# DIY_Arduino_-_REV_1.net
KiCad netlist of a schematic drawn in EAGLE
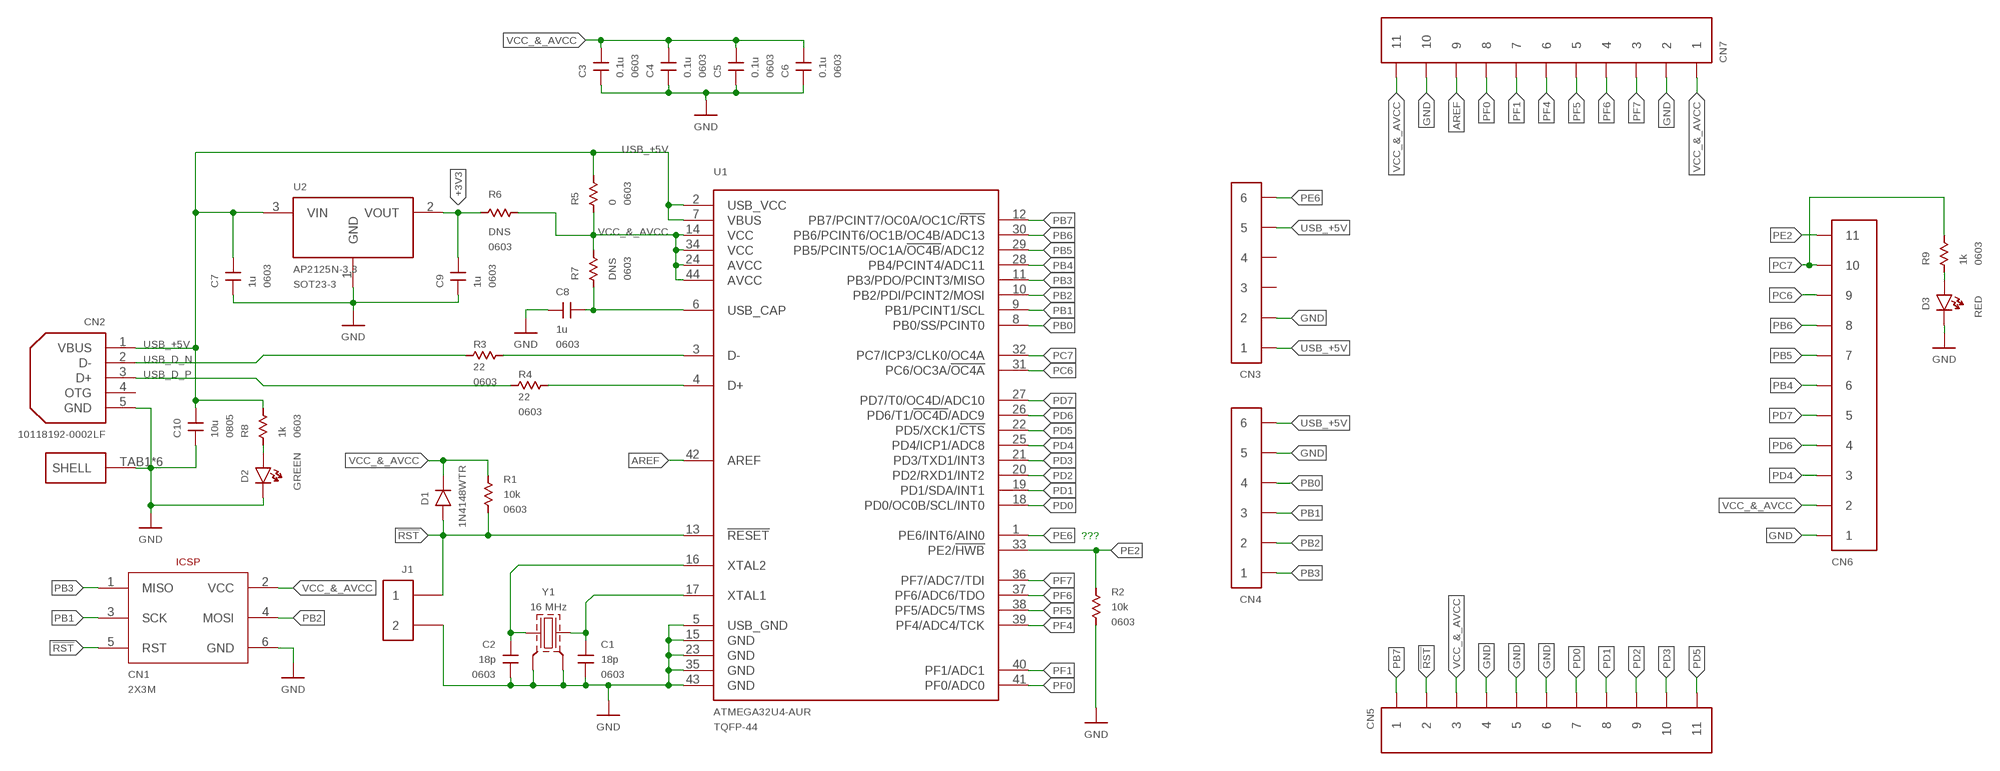
[diagram p0: schematic, sheet 1]

(export (version "E")
  (design (tool "Eeschema 10.0.6"))
  (components
    (comp (ref "C1")
      (value "18p")
      (footprint "eagle-import:EIA0603")
      (fields (field (name "PACKAGE") "0603") (field (name "MPN") "C0603C180J5GACTU"))
      (libsource (lib "eagle-import") (part "C_SMDC0603"))
    )
    (comp (ref "C2")
      (value "18p")
      (footprint "eagle-import:EIA0603")
      (fields (field (name "PACKAGE") "0603") (field (name "MPN") "C0603C180J5GACTU"))
      (libsource (lib "eagle-import") (part "C_SMDC0603"))
    )
    (comp (ref "C3")
      (value "0.1u")
      (footprint "eagle-import:EIA0603")
      (fields (field (name "PACKAGE") "0603") (field (name "MPN") "CL10B104KB8NNNC"))
      (libsource (lib "eagle-import") (part "C_SMDC0603"))
    )
    (comp (ref "C4")
      (value "0.1u")
      (footprint "eagle-import:EIA0603")
      (fields (field (name "PACKAGE") "0603") (field (name "MPN") "CL10B104KB8NNNC"))
      (libsource (lib "eagle-import") (part "C_SMDC0603"))
    )
    (comp (ref "C5")
      (value "0.1u")
      (footprint "eagle-import:EIA0603")
      (fields (field (name "PACKAGE") "0603") (field (name "MPN") "CL10B104KB8NNNC"))
      (libsource (lib "eagle-import") (part "C_SMDC0603"))
    )
    (comp (ref "C6")
      (value "0.1u")
      (footprint "eagle-import:EIA0603")
      (fields (field (name "PACKAGE") "0603") (field (name "MPN") "CL10B104KB8NNNC"))
      (libsource (lib "eagle-import") (part "C_SMDC0603"))
    )
    (comp (ref "C7")
      (value "1u")
      (footprint "eagle-import:EIA0603")
      (fields (field (name "PACKAGE") "0603") (field (name "MPN") "CL10B105KP8NNNC"))
      (libsource (lib "eagle-import") (part "C_SMDC0603"))
    )
    (comp (ref "C8")
      (value "1u")
      (footprint "eagle-import:EIA0603")
      (fields (field (name "PACKAGE") "0603") (field (name "MPN") "CL10B105KP8NNNC"))
      (libsource (lib "eagle-import") (part "C_SMDC0603"))
    )
    (comp (ref "C9")
      (value "1u")
      (footprint "eagle-import:EIA0603")
      (fields (field (name "PACKAGE") "0603") (field (name "MPN") "CL10B105KP8NNNC"))
      (libsource (lib "eagle-import") (part "C_SMDC0603"))
    )
    (comp (ref "C10")
      (value "10u")
      (footprint "eagle-import:EIA0805")
      (fields (field (name "PACKAGE") "0805") (field (name "MPN") "CL21A106KOFNNNE"))
      (libsource (lib "eagle-import") (part "C_SMDC0805"))
    )
    (comp (ref "CN1")
      (value "2X3M")
      (footprint "eagle-import:2X3_100MIL_ICSP")
      (fields (field (name "MPN") "PH2-06-UA"))
      (libsource (lib "eagle-import") (part "2X3_ICSPARDUINO_ICSP"))
    )
    (comp (ref "CN2")
      (value "10118192-0002LF")
      (footprint "eagle-import:AMPHENOL_10118192-0002LF")
      (fields (field (name "MPN") "10118192-0002LF"))
      (libsource (lib "eagle-import") (part "USB_MICRO_B_GENERICSMT"))
    )
    (comp (ref "CN3")
      (value "1X6THRU")
      (footprint "eagle-import:1X6_100MIL_THRU")
      (libsource (lib "eagle-import") (part "1X6THRU"))
    )
    (comp (ref "CN4")
      (value "1X6THRU")
      (footprint "eagle-import:1X6_100MIL_THRU")
      (libsource (lib "eagle-import") (part "1X6THRU"))
    )
    (comp (ref "CN5")
      (value "1X11")
      (footprint "eagle-import:1X11_100MIL_THRU")
      (libsource (lib "eagle-import") (part "1X11"))
    )
    (comp (ref "CN6")
      (value "1X11")
      (footprint "eagle-import:1X11_100MIL_THRU")
      (libsource (lib "eagle-import") (part "1X11"))
    )
    (comp (ref "CN7")
      (value "1X11")
      (footprint "eagle-import:1X11_100MIL_THRU")
      (libsource (lib "eagle-import") (part "1X11"))
    )
    (comp (ref "D1")
      (value "1N4148WTR")
      (footprint "eagle-import:SOD-123")
      (fields (field (name "MPN") "1N4148WTR"))
      (libsource (lib "eagle-import") (part "SILICON"))
    )
    (comp (ref "D2")
      (value "GREEN")
      (footprint "eagle-import:EIA0603_LED")
      (fields (field (name "MPN") "HSME-C191"))
      (libsource (lib "eagle-import") (part "LED_SMD"))
    )
    (comp (ref "D3")
      (value "RED")
      (footprint "eagle-import:EIA0603_LED")
      (fields (field (name "MPN") "ASMT-RR45-AQ902"))
      (libsource (lib "eagle-import") (part "LED_SMD"))
    )
    (comp (ref "J1")
      (value "1X2")
      (footprint "eagle-import:1X2_100MIL_THRU")
      (libsource (lib "eagle-import") (part "1X2"))
    )
    (comp (ref "R1")
      (value "10k")
      (footprint "eagle-import:EIA0603")
      (fields (field (name "PACKAGE") "0603") (field (name "MPN") "ERJ-3EKF1002V"))
      (libsource (lib "eagle-import") (part "R_SMDR0603"))
    )
    (comp (ref "R2")
      (value "10k")
      (footprint "eagle-import:EIA0603")
      (fields (field (name "PACKAGE") "0603") (field (name "MPN") "ERJ-3EKF1002V"))
      (libsource (lib "eagle-import") (part "R_SMDR0603"))
    )
    (comp (ref "R3")
      (value "22")
      (footprint "eagle-import:EIA0603")
      (fields (field (name "PACKAGE") "0603") (field (name "MPN") "ERJ-3EKF22R0V"))
      (libsource (lib "eagle-import") (part "R_SMDR0603"))
    )
    (comp (ref "R4")
      (value "22")
      (footprint "eagle-import:EIA0603")
      (fields (field (name "PACKAGE") "0603") (field (name "MPN") "ERJ-3EKF22R0V"))
      (libsource (lib "eagle-import") (part "R_SMDR0603"))
    )
    (comp (ref "R5")
      (value "0")
      (footprint "eagle-import:EIA0603")
      (fields (field (name "PACKAGE") "0603") (field (name "MPN") "RMCF0603ZT0R00"))
      (libsource (lib "eagle-import") (part "R_SMDR0603"))
    )
    (comp (ref "R6")
      (value "DNS")
      (footprint "eagle-import:EIA0603")
      (fields (field (name "PACKAGE") "0603"))
      (libsource (lib "eagle-import") (part "R_SMDR0603"))
    )
    (comp (ref "R7")
      (value "DNS")
      (footprint "eagle-import:EIA0603")
      (fields (field (name "PACKAGE") "0603"))
      (libsource (lib "eagle-import") (part "R_SMDR0603"))
    )
    (comp (ref "R8")
      (value "1k")
      (footprint "eagle-import:EIA0603")
      (fields (field (name "PACKAGE") "0603") (field (name "MPN") "ERJ-3EKF1001V"))
      (libsource (lib "eagle-import") (part "R_SMDR0603"))
    )
    (comp (ref "R9")
      (value "1k")
      (footprint "eagle-import:EIA0603")
      (fields (field (name "PACKAGE") "0603") (field (name "MPN") "ERJ-3EKF1001V"))
      (libsource (lib "eagle-import") (part "R_SMDR0603"))
    )
    (comp (ref "U1")
      (value "ATMEGA32U4-AUR")
      (footprint "eagle-import:TQFP-44")
      (fields (field (name "PACKAGE") "TQFP-44"))
      (libsource (lib "eagle-import") (part "ATMEGA32U4TQFP-44"))
    )
    (comp (ref "U2")
      (value "AP2125N-3.3")
      (footprint "eagle-import:SOT23-3")
      (fields (field (name "PACKAGE") "SOT23-3") (field (name "MPN") "AP2125N-3.3TRG1"))
      (libsource (lib "eagle-import") (part "AP2125FIXED"))
    )
    (comp (ref "Y1")
      (value "16 MHz")
      (footprint "eagle-import:EPSON_FA-238")
      (fields (field (name "MPN") "FA-238 16.0000MB-C3"))
      (libsource (lib "eagle-import") (part "CRYSTALFA-238"))
    )
  )
  (nets
    (net (code "1") (name "+3V3") (class "Default")
      (node (ref "C9") (pin "P$2") (pinfunction "P$2_P$2") (pintype "passive"))
      (node (ref "R6") (pin "P$1") (pinfunction "P$1_P$1") (pintype "passive"))
      (node (ref "U2") (pin "2") (pinfunction "VOUT_2") (pintype "bidirectional"))
    )
    (net (code "2") (name "/USB_D_N") (class "Default")
      (node (ref "CN2") (pin "2") (pinfunction "D-_2") (pintype "bidirectional"))
      (node (ref "R3") (pin "P$1") (pinfunction "P$1_P$1") (pintype "passive"))
    )
    (net (code "3") (name "/USB_D_P") (class "Default")
      (node (ref "CN2") (pin "3") (pinfunction "D+_3") (pintype "bidirectional"))
      (node (ref "R4") (pin "P$1") (pinfunction "P$1_P$1") (pintype "passive"))
    )
    (net (code "4") (name "/~{RST}") (class "Default")
      (node (ref "CN1") (pin "5") (pinfunction "RST_5") (pintype "bidirectional"))
      (node (ref "CN5") (pin "2") (pinfunction "2_2") (pintype "bidirectional"))
      (node (ref "D1") (pin "A") (pinfunction "A_A") (pintype "bidirectional"))
      (node (ref "J1") (pin "1") (pinfunction "1_1") (pintype "bidirectional"))
      (node (ref "R1") (pin "P$1") (pinfunction "P$1_P$1") (pintype "passive"))
      (node (ref "U1") (pin "13") (pinfunction "~{RESET}_13") (pintype "bidirectional"))
    )
    (net (code "5") (name "AREF") (class "Default")
      (node (ref "CN7") (pin "9") (pinfunction "9_9") (pintype "bidirectional"))
      (node (ref "U1") (pin "42") (pinfunction "AREF_42") (pintype "bidirectional"))
    )
    (net (code "6") (name "GND") (class "Default")
      (node (ref "C1") (pin "P$1") (pinfunction "P$1_P$1") (pintype "passive"))
      (node (ref "C10") (pin "P$1") (pinfunction "P$1_P$1") (pintype "passive"))
      (node (ref "C2") (pin "P$1") (pinfunction "P$1_P$1") (pintype "passive"))
      (node (ref "C3") (pin "P$1") (pinfunction "P$1_P$1") (pintype "passive"))
      (node (ref "C4") (pin "P$1") (pinfunction "P$1_P$1") (pintype "passive"))
      (node (ref "C5") (pin "P$1") (pinfunction "P$1_P$1") (pintype "passive"))
      (node (ref "C6") (pin "P$1") (pinfunction "P$1_P$1") (pintype "passive"))
      (node (ref "C7") (pin "P$1") (pinfunction "P$1_P$1") (pintype "passive"))
      (node (ref "C8") (pin "P$1") (pinfunction "P$1_P$1") (pintype "passive"))
      (node (ref "C9") (pin "P$1") (pinfunction "P$1_P$1") (pintype "passive"))
      (node (ref "CN1") (pin "6") (pinfunction "GND_6") (pintype "bidirectional"))
      (node (ref "CN2") (pin "5") (pinfunction "GND_5") (pintype "bidirectional"))
      (node (ref "CN2") (pin "TAB1") (pinfunction "SHELL_TAB1") (pintype "bidirectional"))
      (node (ref "CN2") (pin "TAB2") (pinfunction "SHELL_TAB2") (pintype "bidirectional"))
      (node (ref "CN2") (pin "TAB3") (pinfunction "SHELL_TAB3") (pintype "bidirectional"))
      (node (ref "CN2") (pin "TAB4") (pinfunction "SHELL_TAB4") (pintype "bidirectional"))
      (node (ref "CN2") (pin "TAB5") (pinfunction "SHELL_TAB5") (pintype "bidirectional"))
      (node (ref "CN2") (pin "TAB6") (pinfunction "SHELL_TAB6") (pintype "bidirectional"))
      (node (ref "CN3") (pin "2") (pinfunction "2_2") (pintype "bidirectional"))
      (node (ref "CN4") (pin "5") (pinfunction "5_5") (pintype "bidirectional"))
      (node (ref "CN5") (pin "4") (pinfunction "4_4") (pintype "bidirectional"))
      (node (ref "CN5") (pin "5") (pinfunction "5_5") (pintype "bidirectional"))
      (node (ref "CN5") (pin "6") (pinfunction "6_6") (pintype "bidirectional"))
      (node (ref "CN6") (pin "1") (pinfunction "1_1") (pintype "bidirectional"))
      (node (ref "CN7") (pin "10") (pinfunction "10_10") (pintype "bidirectional"))
      (node (ref "CN7") (pin "2") (pinfunction "2_2") (pintype "bidirectional"))
      (node (ref "D2") (pin "C") (pinfunction "C_C") (pintype "passive"))
      (node (ref "D3") (pin "C") (pinfunction "C_C") (pintype "passive"))
      (node (ref "J1") (pin "2") (pinfunction "2_2") (pintype "bidirectional"))
      (node (ref "R2") (pin "P$1") (pinfunction "P$1_P$1") (pintype "passive"))
      (node (ref "U1") (pin "15") (pinfunction "GND_15") (pintype "bidirectional"))
      (node (ref "U1") (pin "23") (pinfunction "GND_23") (pintype "bidirectional"))
      (node (ref "U1") (pin "35") (pinfunction "GND_35") (pintype "bidirectional"))
      (node (ref "U1") (pin "43") (pinfunction "GND_43") (pintype "bidirectional"))
      (node (ref "U1") (pin "5") (pinfunction "USB_GND_5") (pintype "bidirectional"))
      (node (ref "U2") (pin "1") (pinfunction "GND_1") (pintype "bidirectional"))
      (node (ref "Y1") (pin "2") (pinfunction "GND_2") (pintype "bidirectional"))
      (node (ref "Y1") (pin "4") (pinfunction "GND_4") (pintype "bidirectional"))
    )
    (net (code "7") (name "Net-(D2-PadA)") (class "Default")
      (node (ref "D2") (pin "A") (pinfunction "A_A") (pintype "passive"))
      (node (ref "R8") (pin "P$1") (pinfunction "P$1_P$1") (pintype "passive"))
    )
    (net (code "8") (name "Net-(D3-PadA)") (class "Default")
      (node (ref "D3") (pin "A") (pinfunction "A_A") (pintype "passive"))
      (node (ref "R9") (pin "P$1") (pinfunction "P$1_P$1") (pintype "passive"))
    )
    (net (code "9") (name "Net-(U1-D+)") (class "Default")
      (node (ref "R4") (pin "P$2") (pinfunction "P$2_P$2") (pintype "passive"))
      (node (ref "U1") (pin "4") (pinfunction "D+_4") (pintype "bidirectional"))
    )
    (net (code "10") (name "Net-(U1-D-)") (class "Default")
      (node (ref "R3") (pin "P$2") (pinfunction "P$2_P$2") (pintype "passive"))
      (node (ref "U1") (pin "3") (pinfunction "D-_3") (pintype "bidirectional"))
    )
    (net (code "11") (name "Net-(U1-USB_CAP)") (class "Default")
      (node (ref "C8") (pin "P$2") (pinfunction "P$2_P$2") (pintype "passive"))
      (node (ref "R7") (pin "P$1") (pinfunction "P$1_P$1") (pintype "passive"))
      (node (ref "U1") (pin "6") (pinfunction "USB_CAP_6") (pintype "bidirectional"))
    )
    (net (code "12") (name "Net-(U1-XTAL1)") (class "Default")
      (node (ref "C1") (pin "P$2") (pinfunction "P$2_P$2") (pintype "passive"))
      (node (ref "U1") (pin "17") (pinfunction "XTAL1_17") (pintype "bidirectional"))
      (node (ref "Y1") (pin "3") (pinfunction "3_3") (pintype "bidirectional"))
    )
    (net (code "13") (name "Net-(U1-XTAL2)") (class "Default")
      (node (ref "C2") (pin "P$2") (pinfunction "P$2_P$2") (pintype "passive"))
      (node (ref "U1") (pin "16") (pinfunction "XTAL2_16") (pintype "bidirectional"))
      (node (ref "Y1") (pin "1") (pinfunction "1_1") (pintype "bidirectional"))
    )
    (net (code "14") (name "PB0") (class "Default")
      (node (ref "CN4") (pin "4") (pinfunction "4_4") (pintype "bidirectional"))
      (node (ref "U1") (pin "8") (pinfunction "PB0/SS/PCINT0_8") (pintype "bidirectional"))
    )
    (net (code "15") (name "PB1") (class "Default")
      (node (ref "CN1") (pin "3") (pinfunction "SCK_3") (pintype "bidirectional"))
      (node (ref "CN4") (pin "3") (pinfunction "3_3") (pintype "bidirectional"))
      (node (ref "U1") (pin "9") (pinfunction "PB1/PCINT1/SCL_9") (pintype "bidirectional"))
    )
    (net (code "16") (name "PB2") (class "Default")
      (node (ref "CN1") (pin "4") (pinfunction "MOSI_4") (pintype "bidirectional"))
      (node (ref "CN4") (pin "2") (pinfunction "2_2") (pintype "bidirectional"))
      (node (ref "U1") (pin "10") (pinfunction "PB2/PDI/PCINT2/MOSI_10") (pintype "bidirectional"))
    )
    (net (code "17") (name "PB3") (class "Default")
      (node (ref "CN1") (pin "1") (pinfunction "MISO_1") (pintype "bidirectional"))
      (node (ref "CN4") (pin "1") (pinfunction "1_1") (pintype "bidirectional"))
      (node (ref "U1") (pin "11") (pinfunction "PB3/PDO/PCINT3/MISO_11") (pintype "bidirectional"))
    )
    (net (code "18") (name "PB4") (class "Default")
      (node (ref "CN6") (pin "6") (pinfunction "6_6") (pintype "bidirectional"))
      (node (ref "U1") (pin "28") (pinfunction "PB4/PCINT4/ADC11_28") (pintype "bidirectional"))
    )
    (net (code "19") (name "PB5") (class "Default")
      (node (ref "CN6") (pin "7") (pinfunction "7_7") (pintype "bidirectional"))
      (node (ref "U1") (pin "29") (pinfunction "PB5/PCINT5/OC1A/~{OC4B}/ADC12_29") (pintype "bidirectional"))
    )
    (net (code "20") (name "PB6") (class "Default")
      (node (ref "CN6") (pin "8") (pinfunction "8_8") (pintype "bidirectional"))
      (node (ref "U1") (pin "30") (pinfunction "PB6/PCINT6/OC1B/OC4B/ADC13_30") (pintype "bidirectional"))
    )
    (net (code "21") (name "PB7") (class "Default")
      (node (ref "CN5") (pin "1") (pinfunction "1_1") (pintype "bidirectional"))
      (node (ref "U1") (pin "12") (pinfunction "PB7/PCINT7/OC0A/OC1C/~{RTS}_12") (pintype "bidirectional"))
    )
    (net (code "22") (name "PC6") (class "Default")
      (node (ref "CN6") (pin "9") (pinfunction "9_9") (pintype "bidirectional"))
      (node (ref "U1") (pin "31") (pinfunction "PC6/OC3A/~{OC4A}_31") (pintype "bidirectional"))
    )
    (net (code "23") (name "PC7") (class "Default")
      (node (ref "CN6") (pin "10") (pinfunction "10_10") (pintype "bidirectional"))
      (node (ref "R9") (pin "P$2") (pinfunction "P$2_P$2") (pintype "passive"))
      (node (ref "U1") (pin "32") (pinfunction "PC7/ICP3/CLK0/OC4A_32") (pintype "bidirectional"))
    )
    (net (code "24") (name "PD0") (class "Default")
      (node (ref "CN5") (pin "7") (pinfunction "7_7") (pintype "bidirectional"))
      (node (ref "U1") (pin "18") (pinfunction "PD0/OC0B/SCL/INT0_18") (pintype "bidirectional"))
    )
    (net (code "25") (name "PD1") (class "Default")
      (node (ref "CN5") (pin "8") (pinfunction "8_8") (pintype "bidirectional"))
      (node (ref "U1") (pin "19") (pinfunction "PD1/SDA/INT1_19") (pintype "bidirectional"))
    )
    (net (code "26") (name "PD2") (class "Default")
      (node (ref "CN5") (pin "9") (pinfunction "9_9") (pintype "bidirectional"))
      (node (ref "U1") (pin "20") (pinfunction "PD2/RXD1/INT2_20") (pintype "bidirectional"))
    )
    (net (code "27") (name "PD3") (class "Default")
      (node (ref "CN5") (pin "10") (pinfunction "10_10") (pintype "bidirectional"))
      (node (ref "U1") (pin "21") (pinfunction "PD3/TXD1/INT3_21") (pintype "bidirectional"))
    )
    (net (code "28") (name "PD4") (class "Default")
      (node (ref "CN6") (pin "3") (pinfunction "3_3") (pintype "bidirectional"))
      (node (ref "U1") (pin "25") (pinfunction "PD4/ICP1/ADC8_25") (pintype "bidirectional"))
    )
    (net (code "29") (name "PD5") (class "Default")
      (node (ref "CN5") (pin "11") (pinfunction "11_11") (pintype "bidirectional"))
      (node (ref "U1") (pin "22") (pinfunction "PD5/XCK1/~{CTS}_22") (pintype "bidirectional"))
    )
    (net (code "30") (name "PD6") (class "Default")
      (node (ref "CN6") (pin "4") (pinfunction "4_4") (pintype "bidirectional"))
      (node (ref "U1") (pin "26") (pinfunction "PD6/T1/~{OC4D}/ADC9_26") (pintype "bidirectional"))
    )
    (net (code "31") (name "PD7") (class "Default")
      (node (ref "CN6") (pin "5") (pinfunction "5_5") (pintype "bidirectional"))
      (node (ref "U1") (pin "27") (pinfunction "PD7/T0/OC4D/ADC10_27") (pintype "bidirectional"))
    )
    (net (code "32") (name "PE2") (class "Default")
      (node (ref "CN6") (pin "11") (pinfunction "11_11") (pintype "bidirectional"))
      (node (ref "R2") (pin "P$2") (pinfunction "P$2_P$2") (pintype "passive"))
      (node (ref "U1") (pin "33") (pinfunction "PE2/~{HWB}_33") (pintype "bidirectional"))
    )
    (net (code "33") (name "PE6") (class "Default")
      (node (ref "CN3") (pin "6") (pinfunction "6_6") (pintype "bidirectional"))
      (node (ref "U1") (pin "1") (pinfunction "PE6/INT6/AIN0_1") (pintype "bidirectional"))
    )
    (net (code "34") (name "PF0") (class "Default")
      (node (ref "CN7") (pin "8") (pinfunction "8_8") (pintype "bidirectional"))
      (node (ref "U1") (pin "41") (pinfunction "PF0/ADC0_41") (pintype "bidirectional"))
    )
    (net (code "35") (name "PF1") (class "Default")
      (node (ref "CN7") (pin "7") (pinfunction "7_7") (pintype "bidirectional"))
      (node (ref "U1") (pin "40") (pinfunction "PF1/ADC1_40") (pintype "bidirectional"))
    )
    (net (code "36") (name "PF4") (class "Default")
      (node (ref "CN7") (pin "6") (pinfunction "6_6") (pintype "bidirectional"))
      (node (ref "U1") (pin "39") (pinfunction "PF4/ADC4/TCK_39") (pintype "bidirectional"))
    )
    (net (code "37") (name "PF5") (class "Default")
      (node (ref "CN7") (pin "5") (pinfunction "5_5") (pintype "bidirectional"))
      (node (ref "U1") (pin "38") (pinfunction "PF5/ADC5/TMS_38") (pintype "bidirectional"))
    )
    (net (code "38") (name "PF6") (class "Default")
      (node (ref "CN7") (pin "4") (pinfunction "4_4") (pintype "bidirectional"))
      (node (ref "U1") (pin "37") (pinfunction "PF6/ADC6/TDO_37") (pintype "bidirectional"))
    )
    (net (code "39") (name "PF7") (class "Default")
      (node (ref "CN7") (pin "3") (pinfunction "3_3") (pintype "bidirectional"))
      (node (ref "U1") (pin "36") (pinfunction "PF7/ADC7/TDI_36") (pintype "bidirectional"))
    )
    (net (code "40") (name "USB_+5V") (class "Default")
      (node (ref "C10") (pin "P$2") (pinfunction "P$2_P$2") (pintype "passive"))
      (node (ref "C7") (pin "P$2") (pinfunction "P$2_P$2") (pintype "passive"))
      (node (ref "CN2") (pin "1") (pinfunction "VBUS_1") (pintype "bidirectional"))
      (node (ref "CN3") (pin "1") (pinfunction "1_1") (pintype "bidirectional"))
      (node (ref "CN3") (pin "5") (pinfunction "5_5") (pintype "bidirectional"))
      (node (ref "CN4") (pin "6") (pinfunction "6_6") (pintype "bidirectional"))
      (node (ref "R5") (pin "P$2") (pinfunction "P$2_P$2") (pintype "passive"))
      (node (ref "R8") (pin "P$2") (pinfunction "P$2_P$2") (pintype "passive"))
      (node (ref "U1") (pin "2") (pinfunction "USB_VCC_2") (pintype "bidirectional"))
      (node (ref "U1") (pin "7") (pinfunction "VBUS_7") (pintype "bidirectional"))
      (node (ref "U2") (pin "3") (pinfunction "VIN_3") (pintype "bidirectional"))
    )
    (net (code "41") (name "VCC_&_AVCC") (class "Default")
      (node (ref "C3") (pin "P$2") (pinfunction "P$2_P$2") (pintype "passive"))
      (node (ref "C4") (pin "P$2") (pinfunction "P$2_P$2") (pintype "passive"))
      (node (ref "C5") (pin "P$2") (pinfunction "P$2_P$2") (pintype "passive"))
      (node (ref "C6") (pin "P$2") (pinfunction "P$2_P$2") (pintype "passive"))
      (node (ref "CN1") (pin "2") (pinfunction "VCC_2") (pintype "bidirectional"))
      (node (ref "CN5") (pin "3") (pinfunction "3_3") (pintype "bidirectional"))
      (node (ref "CN6") (pin "2") (pinfunction "2_2") (pintype "bidirectional"))
      (node (ref "CN7") (pin "1") (pinfunction "1_1") (pintype "bidirectional"))
      (node (ref "CN7") (pin "11") (pinfunction "11_11") (pintype "bidirectional"))
      (node (ref "D1") (pin "C") (pinfunction "C_C") (pintype "bidirectional"))
      (node (ref "R1") (pin "P$2") (pinfunction "P$2_P$2") (pintype "passive"))
      (node (ref "R5") (pin "P$1") (pinfunction "P$1_P$1") (pintype "passive"))
      (node (ref "R6") (pin "P$2") (pinfunction "P$2_P$2") (pintype "passive"))
      (node (ref "R7") (pin "P$2") (pinfunction "P$2_P$2") (pintype "passive"))
      (node (ref "U1") (pin "14") (pinfunction "VCC_14") (pintype "bidirectional"))
      (node (ref "U1") (pin "24") (pinfunction "AVCC_24") (pintype "bidirectional"))
      (node (ref "U1") (pin "34") (pinfunction "VCC_34") (pintype "bidirectional"))
      (node (ref "U1") (pin "44") (pinfunction "AVCC_44") (pintype "bidirectional"))
    )
    (net (code "42") (name "unconnected-(CN2-OTG-Pad4)") (class "Default")
      (node (ref "CN2") (pin "4") (pinfunction "OTG_4") (pintype "bidirectional"))
    )
    (net (code "43") (name "unconnected-(CN3-Pad3)") (class "Default")
      (node (ref "CN3") (pin "3") (pinfunction "3_3") (pintype "bidirectional"))
    )
    (net (code "44") (name "unconnected-(CN3-Pad4)") (class "Default")
      (node (ref "CN3") (pin "4") (pinfunction "4_4") (pintype "bidirectional"))
    )
  )
)
